# LM2576_BOARD.net
KiCad netlist of a schematic drawn in Altium Designer
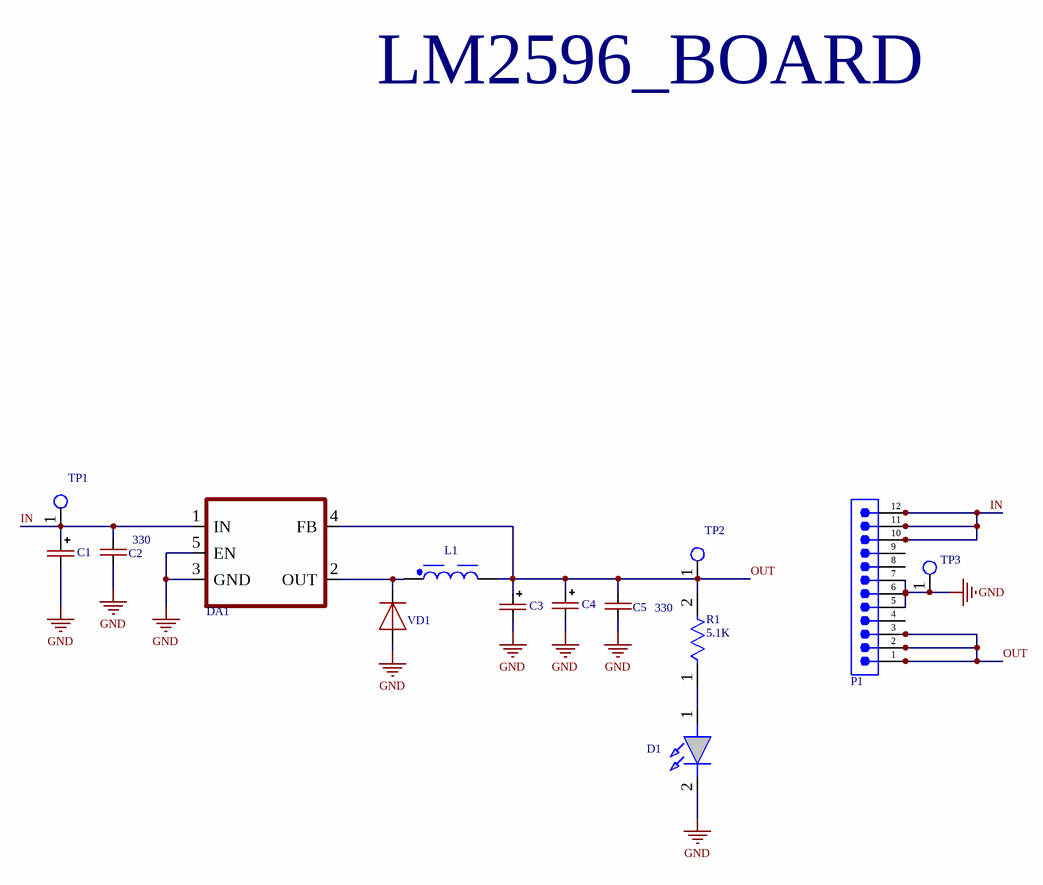
[diagram p0: LM2576_BOARD.SchDoc]

(export (version "E")
  (design (tool "Eeschema 10.0.6"))
  (components
    (comp (ref "C1")
      (value "CAP-POLAR")
      (footprint "SIZE_EEE")
      (libsource (lib "PASSIVE_COMPONENTS") (part "CAP-POLAR"))
    )
    (comp (ref "C2")
      (value "330")
      (footprint "CAP-0805")
      (libsource (lib "PASSIVE_COMPONENTS") (part "CAP-NON-POLAR"))
    )
    (comp (ref "C3")
      (value "CAP-POLAR")
      (footprint "SIZE_EEE")
      (libsource (lib "PASSIVE_COMPONENTS") (part "CAP-POLAR"))
    )
    (comp (ref "C4")
      (value "CAP-POLAR")
      (footprint "SIZE_EEE")
      (libsource (lib "PASSIVE_COMPONENTS") (part "CAP-POLAR"))
    )
    (comp (ref "C5")
      (value "330")
      (footprint "CAP-0805")
      (libsource (lib "PASSIVE_COMPONENTS") (part "CAP-NON-POLAR"))
    )
    (comp (ref "D1")
      (value "151031YS06000")
      (footprint "LED_RED")
      (description "WURTH ELEKTRONIK - 151031YS06000 - LED, Yellow, Through Hole, T-1 (3mm), 30 mA, 2 V, 590 nm")
      (fields (field (name "MOUSER PART NUMBER") "710-151031YS06000"))
      (libsource (lib "Optic-LED") (part "LED"))
    )
    (comp (ref "DA1") (value "LM2576") (footprint "TO-263-5") (libsource (lib "LM2576") (part "LM2576")))
    (comp (ref "L1")
      (value "47µH, 1.17A")
      (footprint "WE-PD2_7850")
      (description "WE-PD2 SMT Power Inductor, size 7850, 47µH, 1.17A, 0.18Ω")
      (fields
        (field (name "MANUFACTURER PART NUMBER") "744775147")
        (field (name "MANUFACTURER") "Wurth Elektronik")
      )
      (libsource (lib "WE-PD2 (rev22d)") (part "744775147"))
    )
    (comp (ref "P1")
      (value "61301211021")
      (footprint "61301211021")
      (description "WR-PHD Pin Header, THT, Angled, pitch 2.54mm, 1 Row, 12P")
      (fields (field (name "MANUFACTURER") "Wurth Elektronik"))
      (libsource (lib "Altium_WR-PHD (rev22b)") (part "61301211021"))
    )
    (comp (ref "R1")
      (value "5.1K")
      (footprint "RES-0805")
      (libsource (lib "PASSIVE_COMPONENTS") (part "RES-CONST"))
    )
    (comp (ref "TP1")
      (value "~")
      (footprint "Test_Point")
      (description "Test_Point")
      (libsource (lib "Connectors") (part "TP_PCB?"))
    )
    (comp (ref "TP2")
      (value "~")
      (footprint "Test_Point")
      (description "Test_Point")
      (libsource (lib "Connectors") (part "TP_PCB?"))
    )
    (comp (ref "TP3")
      (value "~")
      (footprint "Test_Point")
      (description "Test_Point")
      (libsource (lib "Connectors") (part "TP_PCB?"))
    )
    (comp (ref "VD1") (value "DIODE") (footprint "DO-214AB") (libsource (lib "S3M") (part "DIODE")))
  )
  (nets
    (net (code "1") (name "/IN") (class "Default")
      (node (ref "C1") (pin "1") (pinfunction "+_1") (pintype "passive"))
      (node (ref "C2") (pin "2") (pinfunction "2_2") (pintype "passive"))
      (node (ref "DA1") (pin "1") (pinfunction "IN_1") (pintype "passive"))
      (node (ref "P1") (pin "10") (pinfunction "10_10") (pintype "passive"))
      (node (ref "P1") (pin "11") (pinfunction "11_11") (pintype "passive"))
      (node (ref "P1") (pin "12") (pinfunction "12_12") (pintype "passive"))
      (node (ref "TP1") (pin "1") (pinfunction "G9_1") (pintype "passive"))
    )
    (net (code "2") (name "/OUT") (class "Default")
      (node (ref "C3") (pin "1") (pinfunction "+_1") (pintype "passive"))
      (node (ref "C4") (pin "1") (pinfunction "+_1") (pintype "passive"))
      (node (ref "C5") (pin "2") (pinfunction "2_2") (pintype "passive"))
      (node (ref "DA1") (pin "4") (pinfunction "FB_4") (pintype "passive"))
      (node (ref "L1") (pin "2") (pinfunction "2_2") (pintype "passive"))
      (node (ref "P1") (pin "1") (pinfunction "1_1") (pintype "passive"))
      (node (ref "P1") (pin "2") (pinfunction "2_2") (pintype "passive"))
      (node (ref "P1") (pin "3") (pinfunction "3_3") (pintype "passive"))
      (node (ref "R1") (pin "2") (pinfunction "2_2") (pintype "passive"))
      (node (ref "TP2") (pin "1") (pinfunction "G9_1") (pintype "passive"))
    )
    (net (code "3") (name "GND") (class "Default")
      (node (ref "C1") (pin "2") (pinfunction "-_2") (pintype "passive"))
      (node (ref "C2") (pin "1") (pinfunction "1_1") (pintype "passive"))
      (node (ref "C3") (pin "2") (pinfunction "-_2") (pintype "passive"))
      (node (ref "C4") (pin "2") (pinfunction "-_2") (pintype "passive"))
      (node (ref "C5") (pin "1") (pinfunction "1_1") (pintype "passive"))
      (node (ref "D1") (pin "2") (pinfunction "K_2") (pintype "passive"))
      (node (ref "DA1") (pin "3") (pinfunction "GND_3") (pintype "passive"))
      (node (ref "DA1") (pin "5") (pinfunction "EN_5") (pintype "passive"))
      (node (ref "P1") (pin "5") (pinfunction "5_5") (pintype "passive"))
      (node (ref "P1") (pin "6") (pinfunction "6_6") (pintype "passive"))
      (node (ref "P1") (pin "7") (pinfunction "7_7") (pintype "passive"))
      (node (ref "TP3") (pin "1") (pinfunction "G9_1") (pintype "passive"))
      (node (ref "VD1") (pin "2") (pinfunction "A_2") (pintype "passive"))
    )
    (net (code "4") (name "Net-(D1-A)") (class "Default")
      (node (ref "D1") (pin "1") (pinfunction "A_1") (pintype "passive"))
      (node (ref "R1") (pin "1") (pinfunction "1_1") (pintype "passive"))
    )
    (net (code "5") (name "Net-(DA1-OUT)") (class "Default")
      (node (ref "DA1") (pin "2") (pinfunction "OUT_2") (pintype "passive"))
      (node (ref "L1") (pin "1") (pinfunction "1_1") (pintype "passive"))
      (node (ref "VD1") (pin "1") (pinfunction "C_1") (pintype "passive"))
    )
    (net (code "6") (name "unconnected-(P1-Pad4)") (class "Default")
      (node (ref "P1") (pin "4") (pinfunction "4_4") (pintype "passive"))
    )
    (net (code "7") (name "unconnected-(P1-Pad8)") (class "Default")
      (node (ref "P1") (pin "8") (pinfunction "8_8") (pintype "passive"))
    )
    (net (code "8") (name "unconnected-(P1-Pad9)") (class "Default")
      (node (ref "P1") (pin "9") (pinfunction "9_9") (pintype "passive"))
    )
  )
)
